# 3.net
KiCad netlist of a schematic drawn in EAGLE
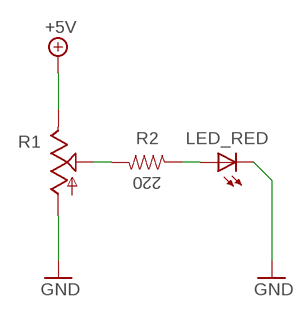
[diagram p0: schematic, sheet 1]
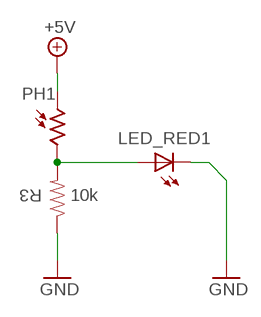
[diagram p1: schematic, sheet 2]

(export (version "E")
  (design (tool "Eeschema 10.0.6"))
  (components
    (comp (ref "LED_RED1")
      (value "LED5MM")
      (footprint "eagle-import:LED5MM")
      (libsource (lib "eagle-import") (part "LED5MM"))
    )
    (comp (ref "PH1")
      (value "A1050_09")
      (footprint "eagle-import:T0-46-A10XX")
      (libsource (lib "eagle-import") (part "A1050_09"))
    )
    (comp (ref "R3")
      (value "10k")
      (footprint "eagle-import:AXIAL-0.3")
      (libsource (lib "eagle-import") (part "100OHM-HORIZ-1/4W-1%"))
    )
    (comp (ref "LED_RED")
      (value "LED5MM")
      (footprint "eagle-import:LED5MM")
      (libsource (lib "eagle-import") (part "LED5MM"))
    )
    (comp (ref "R1")
      (value "TRIM_US-CA14V")
      (footprint "eagle-import:CA14V")
      (libsource (lib "eagle-import") (part "TRIM_US-CA14V"))
    )
    (comp (ref "R2")
      (value "220")
      (footprint "eagle-import:AXIAL-0.3")
      (libsource (lib "eagle-import") (part "100OHM-HORIZ-1/4W-1%"))
    )
  )
  (nets
    (net (code "1") (name "+5V") (class "Default")
      (node (ref "PH1") (pin "1") (pinfunction "1_1") (pintype "passive"))
      (node (ref "R1") (pin "E") (pinfunction "E_E") (pintype "passive"))
    )
    (net (code "2") (name "GND") (class "Default")
      (node (ref "LED_RED") (pin "K") (pinfunction "C_K") (pintype "passive"))
      (node (ref "LED_RED1") (pin "K") (pinfunction "C_K") (pintype "passive"))
      (node (ref "R1") (pin "A") (pinfunction "A_A") (pintype "passive"))
      (node (ref "R3") (pin "P$1") (pinfunction "1_P$1") (pintype "passive"))
    )
    (net (code "3") (name "Net-(R2-1)") (class "Default")
      (node (ref "LED_RED") (pin "A") (pinfunction "A_A") (pintype "passive"))
      (node (ref "R2") (pin "P$1") (pinfunction "1_P$1") (pintype "passive"))
    )
    (net (code "4") (name "Net-(R2-2)") (class "Default")
      (node (ref "R1") (pin "S") (pinfunction "S_S") (pintype "passive"))
      (node (ref "R2") (pin "P$2") (pinfunction "2_P$2") (pintype "passive"))
    )
    (net (code "5") (name "Net-(R3-2)") (class "Default")
      (node (ref "LED_RED1") (pin "A") (pinfunction "A_A") (pintype "passive"))
      (node (ref "PH1") (pin "2") (pinfunction "2_2") (pintype "passive"))
      (node (ref "R3") (pin "P$2") (pinfunction "2_P$2") (pintype "passive"))
    )
  )
)
